# PCBfly.net
KiCad netlist of a schematic drawn in Altium Designer
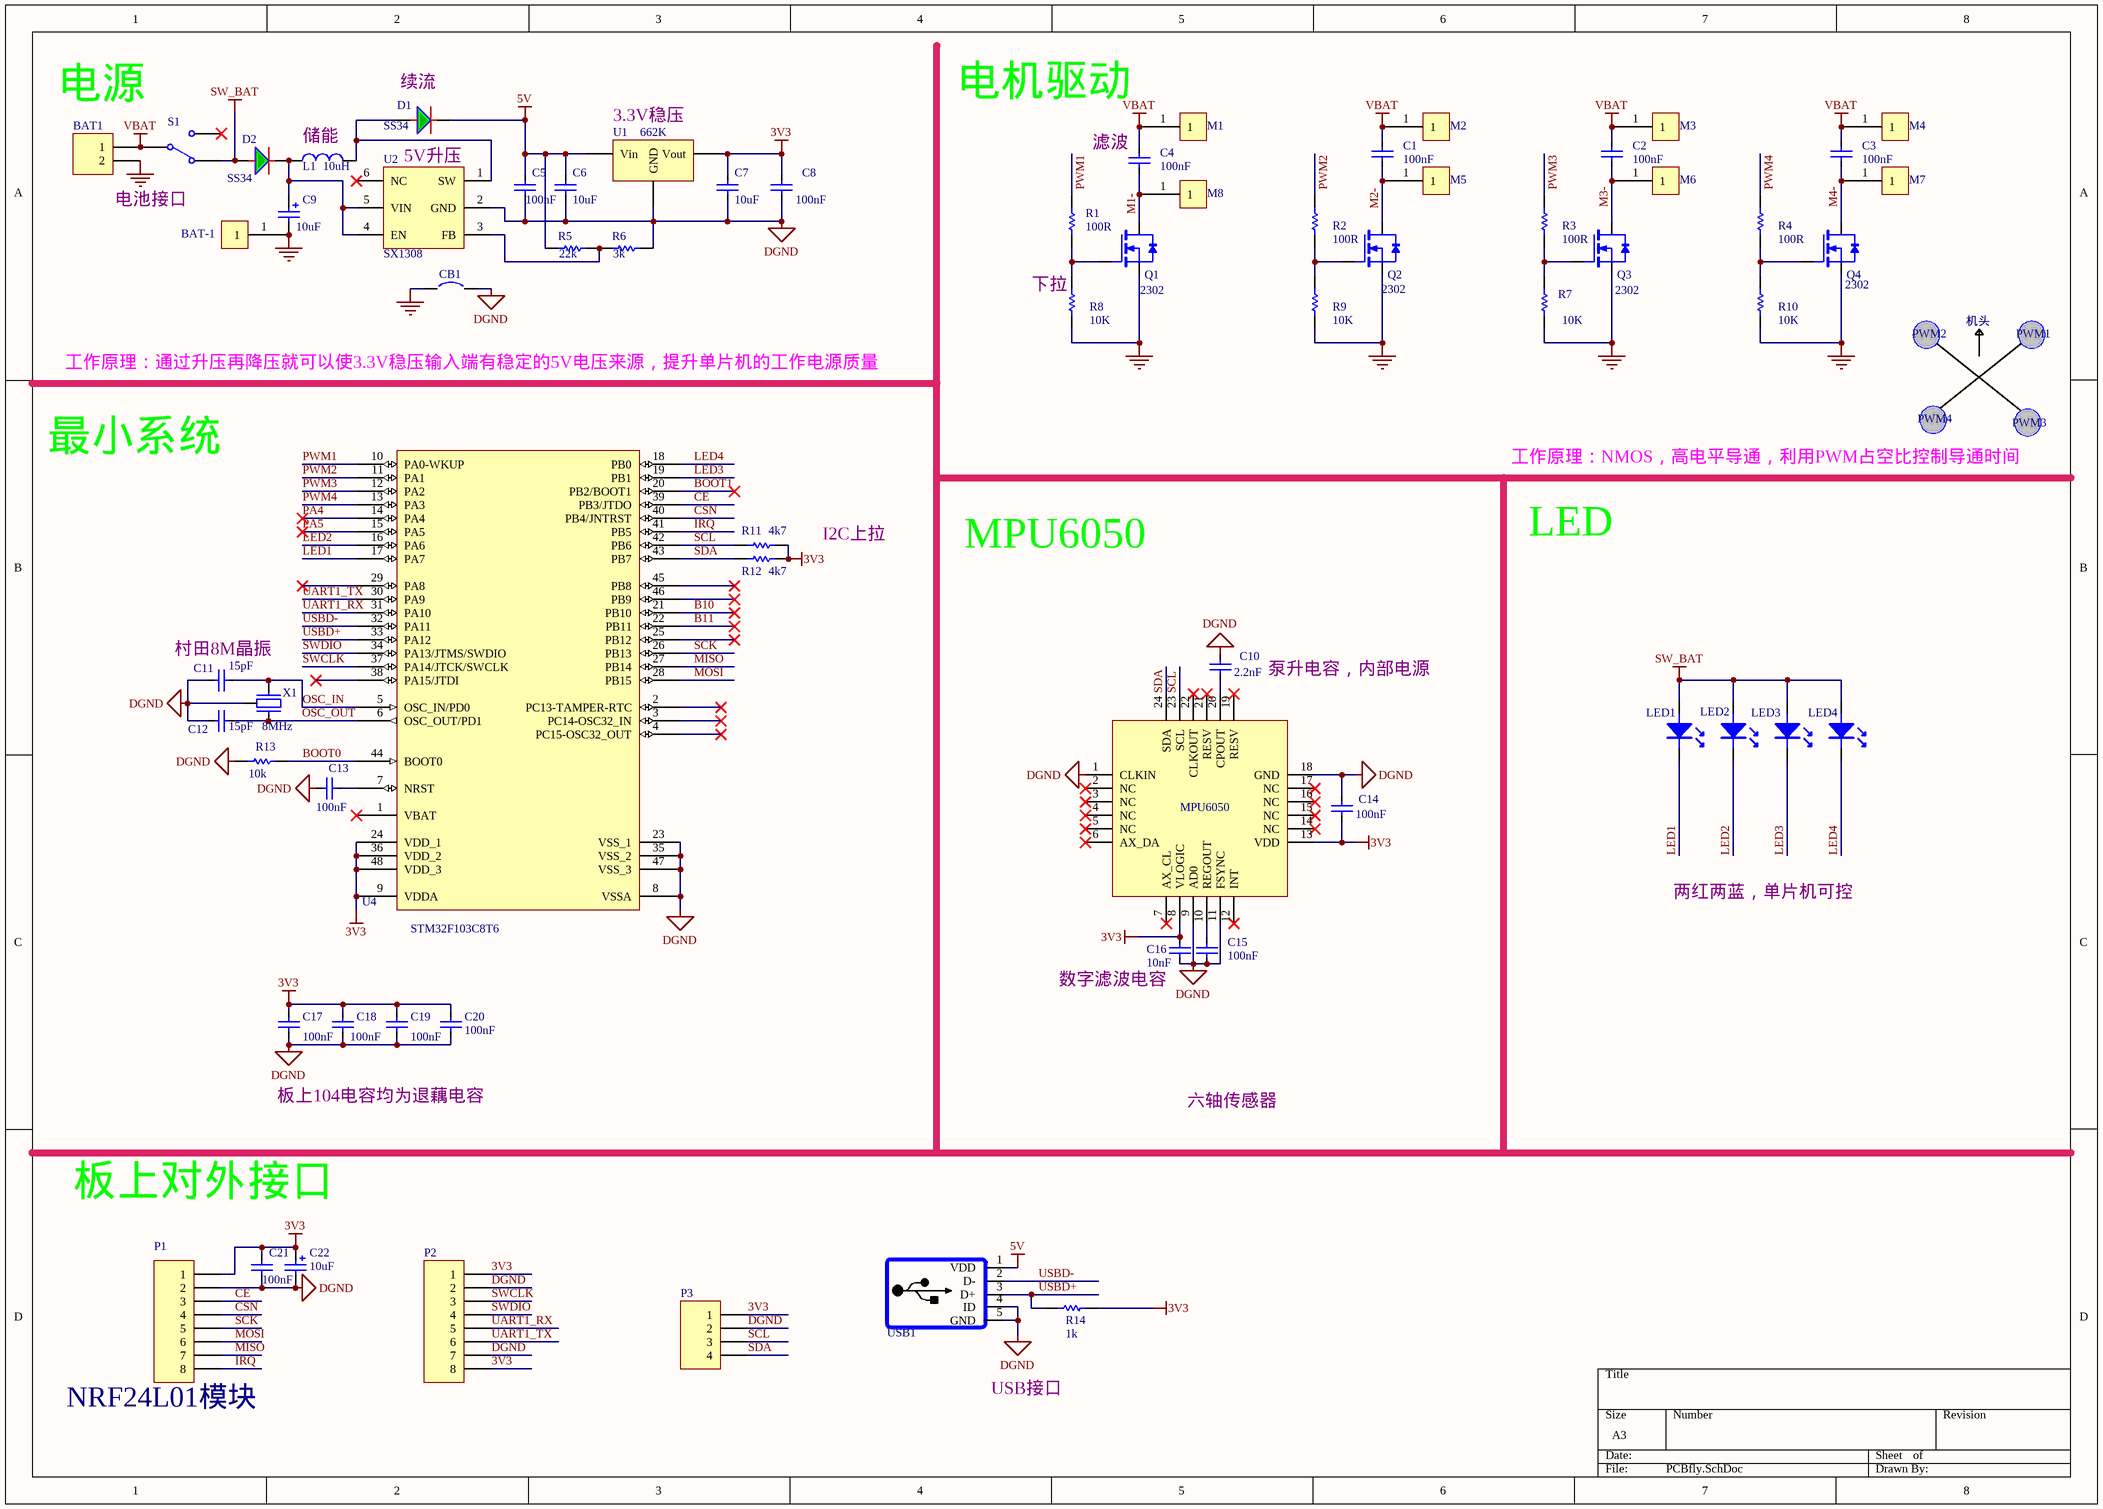
[diagram p0: PCBfly.SchDoc]

(export (version "E")
  (design (tool "Eeschema 10.0.6"))
  (components
    (comp (ref "BAT-1")
      (value "Header 1")
      (footprint "PCBfly:电池接口")
      (libsource (lib "PCBfly") (part "Header 1"))
    )
    (comp (ref "BAT1")
      (value "Header 2")
      (footprint "PCBfly:HDR2")
      (description "Header, 2-Pin")
      (fields (field (name "PUBLISHER") "Altium Limited"))
      (libsource (lib "PCBfly") (part "Header 2"))
    )
    (comp (ref "C1")
      (value "100nF")
      (footprint "PCBfly:0805C")
      (description "Capacitor")
      (libsource (lib "PCBfly") (part "Cap_MLCC"))
    )
    (comp (ref "C2")
      (value "100nF")
      (footprint "PCBfly:0805C")
      (description "Capacitor")
      (libsource (lib "PCBfly") (part "Cap_MLCC"))
    )
    (comp (ref "C3")
      (value "100nF")
      (footprint "PCBfly:0805C")
      (description "Capacitor")
      (libsource (lib "PCBfly") (part "Cap_MLCC"))
    )
    (comp (ref "C4")
      (value "100nF")
      (footprint "PCBfly:0805C")
      (description "Capacitor")
      (libsource (lib "PCBfly") (part "Cap_MLCC"))
    )
    (comp (ref "C5")
      (value "100nF")
      (footprint "PCBfly:0805C")
      (description "Capacitor")
      (libsource (lib "PCBfly") (part "Cap_MLCC"))
    )
    (comp (ref "C6")
      (value "10uF")
      (footprint "PCBfly:0805C")
      (description "Capacitor")
      (libsource (lib "PCBfly") (part "Cap_MLCC"))
    )
    (comp (ref "C7")
      (value "10uF")
      (footprint "PCBfly:0805C")
      (description "Capacitor")
      (libsource (lib "PCBfly") (part "Cap_MLCC"))
    )
    (comp (ref "C8")
      (value "100nF")
      (footprint "PCBfly:0805C")
      (description "Capacitor")
      (libsource (lib "PCBfly") (part "Cap_MLCC"))
    )
    (comp (ref "C9")
      (value "10uF")
      (footprint "PCBfly:CTan(6032)")
      (description "Capacitor")
      (fields (field (name "VOLTAGE") "16V") (field (name "PUBLISHER") "Altium Limited"))
      (libsource (lib "PCBfly") (part "Cap Tan A"))
    )
    (comp (ref "C10")
      (value "2.2nF")
      (footprint "PCBfly:0805C")
      (description "Capacitor")
      (libsource (lib "PCBfly") (part "Cap_MLCC"))
    )
    (comp (ref "C11")
      (value "15pF")
      (footprint "PCBfly:0805C")
      (description "Capacitor")
      (libsource (lib "PCBfly") (part "Cap_MLCC"))
    )
    (comp (ref "C12")
      (value "15pF")
      (footprint "PCBfly:0805C")
      (description "Capacitor")
      (libsource (lib "PCBfly") (part "Cap_MLCC"))
    )
    (comp (ref "C13")
      (value "100nF")
      (footprint "PCBfly:0805C")
      (description "Capacitor")
      (libsource (lib "PCBfly") (part "Cap_MLCC"))
    )
    (comp (ref "C14")
      (value "100nF")
      (footprint "PCBfly:0805C")
      (description "Capacitor")
      (libsource (lib "PCBfly") (part "Cap_MLCC"))
    )
    (comp (ref "C15")
      (value "100nF")
      (footprint "PCBfly:0805C")
      (description "Capacitor")
      (libsource (lib "PCBfly") (part "Cap_MLCC"))
    )
    (comp (ref "C16")
      (value "10nF")
      (footprint "PCBfly:0805C")
      (description "Capacitor")
      (libsource (lib "PCBfly") (part "Cap_MLCC"))
    )
    (comp (ref "C17")
      (value "100nF")
      (footprint "PCBfly:0805C")
      (description "Capacitor")
      (libsource (lib "PCBfly") (part "Cap_MLCC"))
    )
    (comp (ref "C18")
      (value "100nF")
      (footprint "PCBfly:0805C")
      (description "Capacitor")
      (libsource (lib "PCBfly") (part "Cap_MLCC"))
    )
    (comp (ref "C19")
      (value "100nF")
      (footprint "PCBfly:0805C")
      (description "Capacitor")
      (libsource (lib "PCBfly") (part "Cap_MLCC"))
    )
    (comp (ref "C20")
      (value "100nF")
      (footprint "PCBfly:0805C")
      (description "Capacitor")
      (libsource (lib "PCBfly") (part "Cap_MLCC"))
    )
    (comp (ref "C21")
      (value "100nF")
      (footprint "PCBfly:0805C")
      (description "Capacitor")
      (libsource (lib "PCBfly") (part "Cap_MLCC"))
    )
    (comp (ref "C22")
      (value "10uF")
      (footprint "PCBfly:CTan(6032)")
      (description "Capacitor")
      (fields (field (name "VOLTAGE") "16V") (field (name "PUBLISHER") "Altium Limited"))
      (libsource (lib "PCBfly") (part "Cap Tan A"))
    )
    (comp (ref "CB1")
      (value "Circuit Breaker")
      (footprint "PCBfly:JUMP")
      (fields (field (name "PUBLISHER") "Altium Limited"))
      (libsource (lib "PCBfly") (part "Circuit Breaker"))
    )
    (comp (ref "D1") (value "SS34") (footprint "PCBfly:SMA") (libsource (lib "PCBfly") (part "DIODE")))
    (comp (ref "D2") (value "SS34") (footprint "PCBfly:SMA") (libsource (lib "PCBfly") (part "DIODE")))
    (comp (ref "L1")
      (value "10uH")
      (footprint "PCBfly:CD53")
      (description "Inductor")
      (fields (field (name "PUBLISHER") "Altium Limited"))
      (libsource (lib "PCBfly") (part "Inductor Chip"))
    )
    (comp (ref "LED1") (value "LED") (footprint "PCBfly:LED 0805W") (libsource (lib "PCBfly") (part "LED")))
    (comp (ref "LED2") (value "LED") (footprint "PCBfly:LED 0805W") (libsource (lib "PCBfly") (part "LED")))
    (comp (ref "LED3") (value "LED") (footprint "PCBfly:LED 0805W") (libsource (lib "PCBfly") (part "LED")))
    (comp (ref "LED4") (value "LED") (footprint "PCBfly:LED 0805W") (libsource (lib "PCBfly") (part "LED")))
    (comp (ref "M1") (value "Header 1") (footprint "PCBfly:电池接口") (libsource (lib "") (part "Header 1_1")))
    (comp (ref "M2") (value "Header 1") (footprint "PCBfly:电池接口") (libsource (lib "") (part "Header 1_1")))
    (comp (ref "M3") (value "Header 1") (footprint "PCBfly:电池接口") (libsource (lib "") (part "Header 1_1")))
    (comp (ref "M4") (value "Header 1") (footprint "PCBfly:电池接口") (libsource (lib "") (part "Header 1_1")))
    (comp (ref "M5") (value "Header 1") (footprint "PCBfly:电池接口") (libsource (lib "") (part "Header 1_1")))
    (comp (ref "M6") (value "Header 1") (footprint "PCBfly:电池接口") (libsource (lib "") (part "Header 1_1")))
    (comp (ref "M7") (value "Header 1") (footprint "PCBfly:电池接口") (libsource (lib "") (part "Header 1_1")))
    (comp (ref "M8") (value "Header 1") (footprint "PCBfly:电池接口") (libsource (lib "") (part "Header 1_1")))
    (comp (ref "P1")
      (value "NRF24L01模块")
      (footprint "PCBfly:2.4G")
      (description "Header, 8-Pin")
      (fields (field (name "PUBLISHER") "Altium Limited"))
      (libsource (lib "PCBfly") (part "NRF24L01模块"))
    )
    (comp (ref "P2")
      (value "Header 8")
      (footprint "PCBfly:HDR8")
      (description "Header, 8-Pin")
      (fields (field (name "PUBLISHER") "Altium Limited"))
      (libsource (lib "PCBfly") (part "Header 8"))
    )
    (comp (ref "P3")
      (value "Header 4")
      (footprint "PCBfly:HDR2.54-LI-4P")
      (description "Header, 4-Pin")
      (fields (field (name "PUBLISHER") "Altium Limited"))
      (libsource (lib "PCBfly") (part "Header 4"))
    )
    (comp (ref "Q1")
      (value "2302")
      (footprint "PCBfly:NMOS")
      (description "N-Channel Power MOSFET")
      (libsource (lib "PCBfly") (part "N_MOS"))
    )
    (comp (ref "Q2")
      (value "2302")
      (footprint "PCBfly:NMOS")
      (description "N-Channel Power MOSFET")
      (libsource (lib "PCBfly") (part "N_MOS"))
    )
    (comp (ref "Q3")
      (value "2302")
      (footprint "PCBfly:NMOS")
      (description "N-Channel Power MOSFET")
      (libsource (lib "PCBfly") (part "N_MOS"))
    )
    (comp (ref "Q4")
      (value "2302")
      (footprint "PCBfly:NMOS")
      (description "N-Channel Power MOSFET")
      (libsource (lib "PCBfly") (part "N_MOS"))
    )
    (comp (ref "R1")
      (value "100R")
      (footprint "PCBfly:0805R")
      (description "Resistor")
      (fields (field (name "PUBLISHER") "Altium Limited"))
      (libsource (lib "PCBfly") (part "Res"))
    )
    (comp (ref "R2")
      (value "100R")
      (footprint "PCBfly:0805R")
      (description "Resistor")
      (fields (field (name "PUBLISHER") "Altium Limited"))
      (libsource (lib "PCBfly") (part "Res"))
    )
    (comp (ref "R3")
      (value "100R")
      (footprint "PCBfly:0805R")
      (description "Resistor")
      (fields (field (name "PUBLISHER") "Altium Limited"))
      (libsource (lib "PCBfly") (part "Res"))
    )
    (comp (ref "R4")
      (value "100R")
      (footprint "PCBfly:0805R")
      (description "Resistor")
      (fields (field (name "PUBLISHER") "Altium Limited"))
      (libsource (lib "PCBfly") (part "Res"))
    )
    (comp (ref "R5")
      (value "22k")
      (footprint "PCBfly:0805R")
      (description "Resistor")
      (fields (field (name "PUBLISHER") "Altium Limited"))
      (libsource (lib "PCBfly") (part "Res"))
    )
    (comp (ref "R6")
      (value "3k")
      (footprint "PCBfly:0805R")
      (description "Resistor")
      (fields (field (name "PUBLISHER") "Altium Limited"))
      (libsource (lib "PCBfly") (part "Res"))
    )
    (comp (ref "R7")
      (value "10K")
      (footprint "PCBfly:0805R")
      (description "Resistor")
      (fields (field (name "PUBLISHER") "Altium Limited"))
      (libsource (lib "PCBfly") (part "Res"))
    )
    (comp (ref "R8")
      (value "10K")
      (footprint "PCBfly:0805R")
      (description "Resistor")
      (fields (field (name "PUBLISHER") "Altium Limited"))
      (libsource (lib "PCBfly") (part "Res"))
    )
    (comp (ref "R9")
      (value "10K")
      (footprint "PCBfly:0805R")
      (description "Resistor")
      (fields (field (name "PUBLISHER") "Altium Limited"))
      (libsource (lib "PCBfly") (part "Res"))
    )
    (comp (ref "R10")
      (value "10K")
      (footprint "PCBfly:0805R")
      (description "Resistor")
      (fields (field (name "PUBLISHER") "Altium Limited"))
      (libsource (lib "PCBfly") (part "Res"))
    )
    (comp (ref "R11")
      (value "4k7")
      (footprint "PCBfly:0805R")
      (description "Resistor")
      (fields (field (name "PUBLISHER") "Altium Limited"))
      (libsource (lib "PCBfly") (part "Res"))
    )
    (comp (ref "R12")
      (value "4k7")
      (footprint "PCBfly:0805R")
      (description "Resistor")
      (fields (field (name "PUBLISHER") "Altium Limited"))
      (libsource (lib "PCBfly") (part "Res"))
    )
    (comp (ref "R13")
      (value "10k")
      (footprint "PCBfly:0805R")
      (description "Resistor")
      (fields (field (name "PUBLISHER") "Altium Limited"))
      (libsource (lib "PCBfly") (part "Res"))
    )
    (comp (ref "R14")
      (value "1k")
      (footprint "PCBfly:0805R")
      (description "Resistor")
      (fields (field (name "PUBLISHER") "Altium Limited"))
      (libsource (lib "PCBfly") (part "Res"))
    )
    (comp (ref "S1")
      (value "SW-SPDT")
      (footprint "PCBfly:SWITCH")
      (description "SPDT Subminiature Toggle Switch, Right Angle Mounting, Vertical Actuation")
      (fields (field (name "PUBLISHER") "Altium Limited"))
      (libsource (lib "PCBfly") (part "SW-SPDT"))
    )
    (comp (ref "U1")
      (value "662K")
      (footprint "PCBfly:LDO")
      (description "LDO")
      (libsource (lib "PCBfly") (part "LDO"))
    )
    (comp (ref "U2")
      (value "SX1308")
      (footprint "PCBfly:SOT23-6L")
      (libsource (lib "PCBfly") (part "SX1308"))
    )
    (comp (ref "U3") (value "MPU6050") (footprint "PCBfly:QFN24") (libsource (lib "PCBfly") (part "MPU6050")))
    (comp (ref "U4")
      (value "STM32F103C8T6")
      (footprint "PCBfly:LQFP48")
      (libsource (lib "PCBfly") (part "STM32F103C8T6"))
    )
    (comp (ref "USB1") (value "USB") (footprint "PCBfly:USB_micro") (libsource (lib "PCBfly") (part "USB")))
    (comp (ref "X1")
      (value "8MHz")
      (footprint "PCBfly:XTAL_3225-4P")
      (libsource (lib "PCBfly") (part "XTAL_SMT"))
    )
  )
  (nets
    (net (code "1") (name "/B10") (class "Default")
      (node (ref "U4") (pin "21") (pinfunction "PB10_21") (pintype "bidirectional+no_connect"))
    )
    (net (code "2") (name "/B11") (class "Default")
      (node (ref "U4") (pin "22") (pinfunction "PB11_22") (pintype "bidirectional+no_connect"))
    )
    (net (code "3") (name "/BOOT0") (class "Default")
      (node (ref "R13") (pin "1") (pinfunction "1_1") (pintype "passive"))
      (node (ref "U4") (pin "44") (pinfunction "BOOT0_44") (pintype "input"))
    )
    (net (code "4") (name "/BOOT1") (class "Default")
      (node (ref "U4") (pin "20") (pinfunction "PB2/BOOT1_20") (pintype "bidirectional+no_connect"))
    )
    (net (code "5") (name "/CE") (class "Default")
      (node (ref "P1") (pin "3") (pinfunction "3_3") (pintype "passive"))
      (node (ref "U4") (pin "39") (pinfunction "PB3/JTDO_39") (pintype "bidirectional"))
    )
    (net (code "6") (name "/CSN") (class "Default")
      (node (ref "P1") (pin "4") (pinfunction "4_4") (pintype "passive"))
      (node (ref "U4") (pin "40") (pinfunction "PB4/JNTRST_40") (pintype "bidirectional"))
    )
    (net (code "7") (name "/IRQ") (class "Default")
      (node (ref "P1") (pin "8") (pinfunction "8_8") (pintype "passive"))
      (node (ref "U4") (pin "41") (pinfunction "PB5_41") (pintype "bidirectional"))
    )
    (net (code "8") (name "/LED1") (class "Default")
      (node (ref "LED1") (pin "2") (pinfunction "2_2") (pintype "passive"))
      (node (ref "U4") (pin "17") (pinfunction "PA7_17") (pintype "bidirectional"))
    )
    (net (code "9") (name "/LED2") (class "Default")
      (node (ref "LED2") (pin "2") (pinfunction "2_2") (pintype "passive"))
      (node (ref "U4") (pin "16") (pinfunction "PA6_16") (pintype "bidirectional"))
    )
    (net (code "10") (name "/LED3") (class "Default")
      (node (ref "LED3") (pin "2") (pinfunction "2_2") (pintype "passive"))
      (node (ref "U4") (pin "19") (pinfunction "PB1_19") (pintype "bidirectional"))
    )
    (net (code "11") (name "/LED4") (class "Default")
      (node (ref "LED4") (pin "2") (pinfunction "2_2") (pintype "passive"))
      (node (ref "U4") (pin "18") (pinfunction "PB0_18") (pintype "bidirectional"))
    )
    (net (code "12") (name "/M1-") (class "Default")
      (node (ref "C4") (pin "1") (pinfunction "1_1") (pintype "passive"))
      (node (ref "M8") (pin "1") (pinfunction "1_1") (pintype "passive"))
      (node (ref "Q1") (pin "2") (pinfunction "D_2") (pintype "passive"))
    )
    (net (code "13") (name "/M2-") (class "Default")
      (node (ref "C1") (pin "1") (pinfunction "1_1") (pintype "passive"))
      (node (ref "M5") (pin "1") (pinfunction "1_1") (pintype "passive"))
      (node (ref "Q2") (pin "2") (pinfunction "D_2") (pintype "passive"))
    )
    (net (code "14") (name "/M3-") (class "Default")
      (node (ref "C2") (pin "1") (pinfunction "1_1") (pintype "passive"))
      (node (ref "M6") (pin "1") (pinfunction "1_1") (pintype "passive"))
      (node (ref "Q3") (pin "2") (pinfunction "D_2") (pintype "passive"))
    )
    (net (code "15") (name "/M4-") (class "Default")
      (node (ref "C3") (pin "1") (pinfunction "1_1") (pintype "passive"))
      (node (ref "M7") (pin "1") (pinfunction "1_1") (pintype "passive"))
      (node (ref "Q4") (pin "2") (pinfunction "D_2") (pintype "passive"))
    )
    (net (code "16") (name "/MISO") (class "Default")
      (node (ref "P1") (pin "7") (pinfunction "7_7") (pintype "passive"))
      (node (ref "U4") (pin "27") (pinfunction "PB14_27") (pintype "bidirectional"))
    )
    (net (code "17") (name "/MOSI") (class "Default")
      (node (ref "P1") (pin "6") (pinfunction "6_6") (pintype "passive"))
      (node (ref "U4") (pin "28") (pinfunction "PB15_28") (pintype "bidirectional"))
    )
    (net (code "18") (name "/OSC_IN") (class "Default")
      (node (ref "C11") (pin "1") (pinfunction "1_1") (pintype "passive"))
      (node (ref "U4") (pin "5") (pinfunction "OSC_IN/PD0_5") (pintype "input"))
      (node (ref "X1") (pin "3") (pinfunction "3_3") (pintype "passive"))
    )
    (net (code "19") (name "/OSC_OUT") (class "Default")
      (node (ref "C12") (pin "1") (pinfunction "1_1") (pintype "passive"))
      (node (ref "U4") (pin "6") (pinfunction "OSC_OUT/PD1_6") (pintype "output"))
      (node (ref "X1") (pin "1") (pinfunction "1_1") (pintype "passive"))
    )
    (net (code "20") (name "/PA4") (class "Default")
      (node (ref "U4") (pin "14") (pinfunction "PA4_14") (pintype "bidirectional+no_connect"))
    )
    (net (code "21") (name "/PA5") (class "Default")
      (node (ref "U4") (pin "15") (pinfunction "PA5_15") (pintype "bidirectional+no_connect"))
    )
    (net (code "22") (name "/PWM1") (class "Default")
      (node (ref "R1") (pin "2") (pinfunction "2_2") (pintype "passive"))
      (node (ref "U4") (pin "10") (pinfunction "PA0-WKUP_10") (pintype "bidirectional"))
    )
    (net (code "23") (name "/PWM2") (class "Default")
      (node (ref "R2") (pin "2") (pinfunction "2_2") (pintype "passive"))
      (node (ref "U4") (pin "11") (pinfunction "PA1_11") (pintype "bidirectional"))
    )
    (net (code "24") (name "/PWM3") (class "Default")
      (node (ref "R3") (pin "2") (pinfunction "2_2") (pintype "passive"))
      (node (ref "U4") (pin "12") (pinfunction "PA2_12") (pintype "bidirectional"))
    )
    (net (code "25") (name "/PWM4") (class "Default")
      (node (ref "R4") (pin "2") (pinfunction "2_2") (pintype "passive"))
      (node (ref "U4") (pin "13") (pinfunction "PA3_13") (pintype "bidirectional"))
    )
    (net (code "26") (name "/SCK") (class "Default")
      (node (ref "P1") (pin "5") (pinfunction "5_5") (pintype "passive"))
      (node (ref "U4") (pin "26") (pinfunction "PB13_26") (pintype "bidirectional"))
    )
    (net (code "27") (name "/SCL") (class "Default")
      (node (ref "P3") (pin "3") (pinfunction "3_3") (pintype "passive"))
      (node (ref "R11") (pin "2") (pinfunction "2_2") (pintype "passive"))
      (node (ref "U3") (pin "23") (pinfunction "SCL_23") (pintype "passive"))
      (node (ref "U4") (pin "42") (pinfunction "PB6_42") (pintype "bidirectional"))
    )
    (net (code "28") (name "/SDA") (class "Default")
      (node (ref "P3") (pin "4") (pinfunction "4_4") (pintype "passive"))
      (node (ref "R12") (pin "2") (pinfunction "2_2") (pintype "passive"))
      (node (ref "U3") (pin "24") (pinfunction "SDA_24") (pintype "passive"))
      (node (ref "U4") (pin "43") (pinfunction "PB7_43") (pintype "bidirectional"))
    )
    (net (code "29") (name "/SWCLK") (class "Default")
      (node (ref "P2") (pin "3") (pinfunction "3_3") (pintype "passive"))
      (node (ref "U4") (pin "37") (pinfunction "PA14/JTCK/SWCLK_37") (pintype "bidirectional"))
    )
    (net (code "30") (name "/SWDIO") (class "Default")
      (node (ref "P2") (pin "4") (pinfunction "4_4") (pintype "passive"))
      (node (ref "U4") (pin "34") (pinfunction "PA13/JTMS/SWDIO_34") (pintype "bidirectional"))
    )
    (net (code "31") (name "/UART1_RX") (class "Default")
      (node (ref "P2") (pin "5") (pinfunction "5_5") (pintype "passive"))
      (node (ref "U4") (pin "31") (pinfunction "PA10_31") (pintype "bidirectional"))
    )
    (net (code "32") (name "/UART1_TX") (class "Default")
      (node (ref "P2") (pin "6") (pinfunction "6_6") (pintype "passive"))
      (node (ref "U4") (pin "30") (pinfunction "PA9_30") (pintype "bidirectional"))
    )
    (net (code "33") (name "/USBD+") (class "Default")
      (node (ref "R14") (pin "2") (pinfunction "2_2") (pintype "passive"))
      (node (ref "U4") (pin "33") (pinfunction "PA12_33") (pintype "bidirectional"))
      (node (ref "USB1") (pin "3") (pinfunction "D+_3") (pintype "passive"))
    )
    (net (code "34") (name "/USBD-") (class "Default")
      (node (ref "U4") (pin "32") (pinfunction "PA11_32") (pintype "bidirectional"))
      (node (ref "USB1") (pin "2") (pinfunction "D-_2") (pintype "passive"))
    )
    (net (code "35") (name "3V3") (class "Default")
      (node (ref "C14") (pin "1") (pinfunction "1_1") (pintype "passive"))
      (node (ref "C16") (pin "2") (pinfunction "2_2") (pintype "passive"))
      (node (ref "C17") (pin "1") (pinfunction "1_1") (pintype "passive"))
      (node (ref "C18") (pin "1") (pinfunction "1_1") (pintype "passive"))
      (node (ref "C19") (pin "1") (pinfunction "1_1") (pintype "passive"))
      (node (ref "C20") (pin "1") (pinfunction "1_1") (pintype "passive"))
      (node (ref "C21") (pin "1") (pinfunction "1_1") (pintype "passive"))
      (node (ref "C22") (pin "2") (pinfunction "1_2") (pintype "passive"))
      (node (ref "C7") (pin "1") (pinfunction "1_1") (pintype "passive"))
      (node (ref "C8") (pin "1") (pinfunction "1_1") (pintype "passive"))
      (node (ref "P1") (pin "1") (pinfunction "1_1") (pintype "passive"))
      (node (ref "P2") (pin "1") (pinfunction "1_1") (pintype "passive"))
      (node (ref "P2") (pin "8") (pinfunction "8_8") (pintype "passive"))
      (node (ref "P3") (pin "1") (pinfunction "1_1") (pintype "passive"))
      (node (ref "R11") (pin "1") (pinfunction "1_1") (pintype "passive"))
      (node (ref "R12") (pin "1") (pinfunction "1_1") (pintype "passive"))
      (node (ref "R14") (pin "1") (pinfunction "1_1") (pintype "passive"))
      (node (ref "U1") (pin "2") (pinfunction "Vout_2") (pintype "passive"))
      (node (ref "U3") (pin "13") (pinfunction "VDD_13") (pintype "passive"))
      (node (ref "U3") (pin "8") (pinfunction "VLOGIC_8") (pintype "passive"))
      (node (ref "U4") (pin "24") (pinfunction "VDD_1_24") (pintype "power_in"))
      (node (ref "U4") (pin "36") (pinfunction "VDD_2_36") (pintype "power_in"))
      (node (ref "U4") (pin "48") (pinfunction "VDD_3_48") (pintype "power_in"))
      (node (ref "U4") (pin "9") (pinfunction "VDDA_9") (pintype "power_in"))
    )
    (net (code "36") (name "5V") (class "Default")
      (node (ref "C5") (pin "1") (pinfunction "1_1") (pintype "passive"))
      (node (ref "C6") (pin "1") (pinfunction "1_1") (pintype "passive"))
      (node (ref "D1") (pin "2") (pinfunction "2_2") (pintype "passive"))
      (node (ref "R5") (pin "1") (pinfunction "1_1") (pintype "passive"))
      (node (ref "U1") (pin "3") (pinfunction "Vin_3") (pintype "passive"))
      (node (ref "USB1") (pin "1") (pinfunction "VDD_1") (pintype "passive"))
    )
    (net (code "37") (name "DGND") (class "Default")
      (node (ref "C10") (pin "2") (pinfunction "2_2") (pintype "passive"))
      (node (ref "C11") (pin "2") (pinfunction "2_2") (pintype "passive"))
      (node (ref "C12") (pin "2") (pinfunction "2_2") (pintype "passive"))
      (node (ref "C13") (pin "1") (pinfunction "1_1") (pintype "passive"))
      (node (ref "C14") (pin "2") (pinfunction "2_2") (pintype "passive"))
      (node (ref "C15") (pin "1") (pinfunction "1_1") (pintype "passive"))
      (node (ref "C16") (pin "1") (pinfunction "1_1") (pintype "passive"))
      (node (ref "C17") (pin "2") (pinfunction "2_2") (pintype "passive"))
      (node (ref "C18") (pin "2") (pinfunction "2_2") (pintype "passive"))
      (node (ref "C19") (pin "2") (pinfunction "2_2") (pintype "passive"))
      (node (ref "C20") (pin "2") (pinfunction "2_2") (pintype "passive"))
      (node (ref "C21") (pin "2") (pinfunction "2_2") (pintype "passive"))
      (node (ref "C22") (pin "1") (pinfunction "2_1") (pintype "passive"))
      (node (ref "C5") (pin "2") (pinfunction "2_2") (pintype "passive"))
      (node (ref "C6") (pin "2") (pinfunction "2_2") (pintype "passive"))
      (node (ref "C7") (pin "2") (pinfunction "2_2") (pintype "passive"))
      (node (ref "C8") (pin "2") (pinfunction "2_2") (pintype "passive"))
      (node (ref "CB1") (pin "2") (pinfunction "2_2") (pintype "passive"))
      (node (ref "P1") (pin "2") (pinfunction "2_2") (pintype "passive"))
      (node (ref "P2") (pin "2") (pinfunction "2_2") (pintype "passive"))
      (node (ref "P2") (pin "7") (pinfunction "7_7") (pintype "passive"))
      (node (ref "P3") (pin "2") (pinfunction "2_2") (pintype "passive"))
      (node (ref "R13") (pin "2") (pinfunction "2_2") (pintype "passive"))
      (node (ref "R6") (pin "1") (pinfunction "1_1") (pintype "passive"))
      (node (ref "U1") (pin "1") (pinfunction "GND_1") (pintype "passive"))
      (node (ref "U2") (pin "2") (pinfunction "GND_2") (pintype "power_in"))
      (node (ref "U3") (pin "1") (pinfunction "CLKIN_1") (pintype "passive"))
      (node (ref "U3") (pin "11") (pinfunction "FSYNC_11") (pintype "passive"))
      (node (ref "U3") (pin "18") (pinfunction "GND_18") (pintype "passive"))
      (node (ref "U3") (pin "9") (pinfunction "AD0_9") (pintype "passive"))
      (node (ref "U4") (pin "23") (pinfunction "VSS_1_23") (pintype "power_in"))
      (node (ref "U4") (pin "35") (pinfunction "VSS_2_35") (pintype "power_in"))
      (node (ref "U4") (pin "47") (pinfunction "VSS_3_47") (pintype "power_in"))
      (node (ref "U4") (pin "8") (pinfunction "VSSA_8") (pintype "power_in"))
      (node (ref "USB1") (pin "4") (pinfunction "ID_4") (pintype "passive"))
      (node (ref "USB1") (pin "5") (pinfunction "GND_5") (pintype "passive"))
      (node (ref "X1") (pin "2") (pinfunction "2_2") (pintype "passive"))
    )
    (net (code "38") (name "GND") (class "Default")
      (node (ref "BAT-1") (pin "1") (pinfunction "1_1") (pintype "passive"))
      (node (ref "BAT1") (pin "2") (pinfunction "2_2") (pintype "passive"))
      (node (ref "C9") (pin "1") (pinfunction "2_1") (pintype "passive"))
      (node (ref "CB1") (pin "1") (pinfunction "1_1") (pintype "passive"))
      (node (ref "Q1") (pin "3") (pinfunction "S_3") (pintype "passive"))
      (node (ref "Q2") (pin "3") (pinfunction "S_3") (pintype "passive"))
      (node (ref "Q3") (pin "3") (pinfunction "S_3") (pintype "passive"))
      (node (ref "Q4") (pin "3") (pinfunction "S_3") (pintype "passive"))
      (node (ref "R10") (pin "1") (pinfunction "1_1") (pintype "passive"))
      (node (ref "R7") (pin "1") (pinfunction "1_1") (pintype "passive"))
      (node (ref "R8") (pin "1") (pinfunction "1_1") (pintype "passive"))
      (node (ref "R9") (pin "1") (pinfunction "1_1") (pintype "passive"))
    )
    (net (code "39") (name "Net-(C9-1)") (class "Default")
      (node (ref "C9") (pin "2") (pinfunction "1_2") (pintype "passive"))
      (node (ref "D2") (pin "2") (pinfunction "2_2") (pintype "passive"))
      (node (ref "L1") (pin "1") (pinfunction "1_1") (pintype "passive"))
      (node (ref "U2") (pin "4") (pinfunction "EN_4") (pintype "passive"))
      (node (ref "U2") (pin "5") (pinfunction "VIN_5") (pintype "passive"))
    )
    (net (code "40") (name "Net-(Q1-G)") (class "Default")
      (node (ref "Q1") (pin "1") (pinfunction "G_1") (pintype "passive"))
      (node (ref "R1") (pin "1") (pinfunction "1_1") (pintype "passive"))
      (node (ref "R8") (pin "2") (pinfunction "2_2") (pintype "passive"))
    )
    (net (code "41") (name "Net-(Q2-G)") (class "Default")
      (node (ref "Q2") (pin "1") (pinfunction "G_1") (pintype "passive"))
      (node (ref "R2") (pin "1") (pinfunction "1_1") (pintype "passive"))
      (node (ref "R9") (pin "2") (pinfunction "2_2") (pintype "passive"))
    )
    (net (code "42") (name "Net-(Q3-G)") (class "Default")
      (node (ref "Q3") (pin "1") (pinfunction "G_1") (pintype "passive"))
      (node (ref "R3") (pin "1") (pinfunction "1_1") (pintype "passive"))
      (node (ref "R7") (pin "2") (pinfunction "2_2") (pintype "passive"))
    )
    (net (code "43") (name "Net-(Q4-G)") (class "Default")
      (node (ref "Q4") (pin "1") (pinfunction "G_1") (pintype "passive"))
      (node (ref "R10") (pin "2") (pinfunction "2_2") (pintype "passive"))
      (node (ref "R4") (pin "1") (pinfunction "1_1") (pintype "passive"))
    )
    (net (code "44") (name "Net-(U2-FB)") (class "Default")
      (node (ref "R5") (pin "2") (pinfunction "2_2") (pintype "passive"))
      (node (ref "R6") (pin "2") (pinfunction "2_2") (pintype "passive"))
      (node (ref "U2") (pin "3") (pinfunction "FB_3") (pintype "power_in"))
    )
    (net (code "45") (name "Net-(U2-SW)") (class "Default")
      (node (ref "D1") (pin "1") (pinfunction "1_1") (pintype "passive"))
      (node (ref "L1") (pin "2") (pinfunction "2_2") (pintype "passive"))
      (node (ref "U2") (pin "1") (pinfunction "SW_1") (pintype "power_in"))
    )
    (net (code "46") (name "Net-(U3-CPOUT)") (class "Default")
      (node (ref "C10") (pin "1") (pinfunction "1_1") (pintype "passive"))
      (node (ref "U3") (pin "20") (pinfunction "CPOUT_20") (pintype "passive"))
    )
    (net (code "47") (name "Net-(U3-REGOUT)") (class "Default")
      (node (ref "C15") (pin "2") (pinfunction "2_2") (pintype "passive"))
      (node (ref "U3") (pin "10") (pinfunction "REGOUT_10") (pintype "passive"))
    )
    (net (code "48") (name "Net-(U4-NRST)") (class "Default")
      (node (ref "C13") (pin "2") (pinfunction "2_2") (pintype "passive"))
      (node (ref "U4") (pin "7") (pinfunction "NRST_7") (pintype "bidirectional"))
    )
    (net (code "49") (name "SW_BAT") (class "Default")
      (node (ref "D2") (pin "1") (pinfunction "1_1") (pintype "passive"))
      (node (ref "LED1") (pin "1") (pinfunction "1_1") (pintype "passive"))
      (node (ref "LED2") (pin "1") (pinfunction "1_1") (pintype "passive"))
      (node (ref "LED3") (pin "1") (pinfunction "1_1") (pintype "passive"))
      (node (ref "LED4") (pin "1") (pinfunction "1_1") (pintype "passive"))
      (node (ref "S1") (pin "3") (pinfunction "3_3") (pintype "passive"))
    )
    (net (code "50") (name "VBAT") (class "Default")
      (node (ref "BAT1") (pin "1") (pinfunction "1_1") (pintype "passive"))
      (node (ref "C1") (pin "2") (pinfunction "2_2") (pintype "passive"))
      (node (ref "C2") (pin "2") (pinfunction "2_2") (pintype "passive"))
      (node (ref "C3") (pin "2") (pinfunction "2_2") (pintype "passive"))
      (node (ref "C4") (pin "2") (pinfunction "2_2") (pintype "passive"))
      (node (ref "M1") (pin "1") (pinfunction "1_1") (pintype "passive"))
      (node (ref "M2") (pin "1") (pinfunction "1_1") (pintype "passive"))
      (node (ref "M3") (pin "1") (pinfunction "1_1") (pintype "passive"))
      (node (ref "M4") (pin "1") (pinfunction "1_1") (pintype "passive"))
      (node (ref "S1") (pin "2") (pinfunction "2_2") (pintype "passive"))
    )
    (net (code "51") (name "unconnected-(S1-Pad1)") (class "Default")
      (node (ref "S1") (pin "1") (pinfunction "1_1") (pintype "passive+no_connect"))
    )
    (net (code "52") (name "unconnected-(U2-NC-Pad6)") (class "Default")
      (node (ref "U2") (pin "6") (pinfunction "NC_6") (pintype "passive+no_connect"))
    )
    (net (code "53") (name "unconnected-(U3-AX_CL-Pad7)") (class "Default")
      (node (ref "U3") (pin "7") (pinfunction "AX_CL_7") (pintype "passive+no_connect"))
    )
    (net (code "54") (name "unconnected-(U3-AX_DA-Pad6)") (class "Default")
      (node (ref "U3") (pin "6") (pinfunction "AX_DA_6") (pintype "passive+no_connect"))
    )
    (net (code "55") (name "unconnected-(U3-CLKOUT-Pad22)") (class "Default")
      (node (ref "U3") (pin "22") (pinfunction "CLKOUT_22") (pintype "passive+no_connect"))
    )
    (net (code "56") (name "unconnected-(U3-INT-Pad12)") (class "Default")
      (node (ref "U3") (pin "12") (pinfunction "INT_12") (pintype "passive+no_connect"))
    )
    (net (code "57") (name "unconnected-(U3-NC-Pad2)") (class "Default")
      (node (ref "U3") (pin "2") (pinfunction "NC_2") (pintype "passive+no_connect"))
    )
    (net (code "58") (name "unconnected-(U3-NC-Pad3)") (class "Default")
      (node (ref "U3") (pin "3") (pinfunction "NC_3") (pintype "passive+no_connect"))
    )
    (net (code "59") (name "unconnected-(U3-NC-Pad4)") (class "Default")
      (node (ref "U3") (pin "4") (pinfunction "NC_4") (pintype "passive+no_connect"))
    )
    (net (code "60") (name "unconnected-(U3-NC-Pad5)") (class "Default")
      (node (ref "U3") (pin "5") (pinfunction "NC_5") (pintype "passive+no_connect"))
    )
    (net (code "61") (name "unconnected-(U3-NC-Pad14)") (class "Default")
      (node (ref "U3") (pin "14") (pinfunction "NC_14") (pintype "passive+no_connect"))
    )
    (net (code "62") (name "unconnected-(U3-NC-Pad15)") (class "Default")
      (node (ref "U3") (pin "15") (pinfunction "NC_15") (pintype "passive+no_connect"))
    )
    (net (code "63") (name "unconnected-(U3-NC-Pad16)") (class "Default")
      (node (ref "U3") (pin "16") (pinfunction "NC_16") (pintype "passive+no_connect"))
    )
    (net (code "64") (name "unconnected-(U3-NC-Pad17)") (class "Default")
      (node (ref "U3") (pin "17") (pinfunction "NC_17") (pintype "passive+no_connect"))
    )
    (net (code "65") (name "unconnected-(U3-RESV-Pad19)") (class "Default")
      (node (ref "U3") (pin "19") (pinfunction "RESV_19") (pintype "passive+no_connect"))
    )
    (net (code "66") (name "unconnected-(U3-RESV-Pad21)") (class "Default")
      (node (ref "U3") (pin "21") (pinfunction "RESV_21") (pintype "passive+no_connect"))
    )
    (net (code "67") (name "unconnected-(U4-PA8-Pad29)") (class "Default")
      (node (ref "U4") (pin "29") (pinfunction "PA8_29") (pintype "bidirectional+no_connect"))
    )
    (net (code "68") (name "unconnected-(U4-PA15{slash}JTDI-Pad38)") (class "Default")
      (node (ref "U4") (pin "38") (pinfunction "PA15/JTDI_38") (pintype "bidirectional+no_connect"))
    )
    (net (code "69") (name "unconnected-(U4-PB8-Pad45)") (class "Default")
      (node (ref "U4") (pin "45") (pinfunction "PB8_45") (pintype "bidirectional+no_connect"))
    )
    (net (code "70") (name "unconnected-(U4-PB9-Pad46)") (class "Default")
      (node (ref "U4") (pin "46") (pinfunction "PB9_46") (pintype "bidirectional+no_connect"))
    )
    (net (code "71") (name "unconnected-(U4-PB12-Pad25)") (class "Default")
      (node (ref "U4") (pin "25") (pinfunction "PB12_25") (pintype "bidirectional+no_connect"))
    )
    (net (code "72") (name "unconnected-(U4-PC13-TAMPER-RTC-Pad2)") (class "Default")
      (node (ref "U4") (pin "2") (pinfunction "PC13-TAMPER-RTC_2") (pintype "bidirectional+no_connect"))
    )
    (net (code "73") (name "unconnected-(U4-PC14-OSC32_IN-Pad3)") (class "Default")
      (node (ref "U4") (pin "3") (pinfunction "PC14-OSC32_IN_3") (pintype "bidirectional+no_connect"))
    )
    (net (code "74") (name "unconnected-(U4-PC15-OSC32_OUT-Pad4)") (class "Default")
      (node (ref "U4") (pin "4") (pinfunction "PC15-OSC32_OUT_4") (pintype "bidirectional+no_connect"))
    )
    (net (code "75") (name "unconnected-(U4-VBAT-Pad1)") (class "Default")
      (node (ref "U4") (pin "1") (pinfunction "VBAT_1") (pintype "power_in+no_connect"))
    )
  )
)
